# 03_MCU.net
KiCad netlist of a schematic drawn in Altium Designer
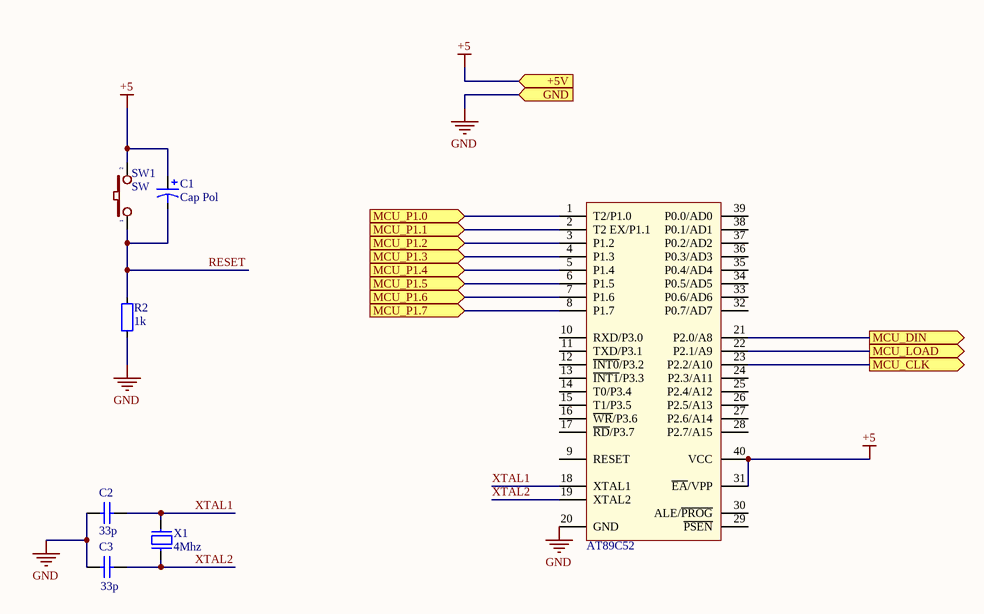
[diagram p0: [03] MCU.SchDoc]

(export (version "E")
  (design (tool "Eeschema 10.0.6"))
  (components
    (comp (ref "C1")
      (value "Cap Pol")
      (footprint "C3MM")
      (description "Polarized Capacitor (Axial)")
      (fields (field (name "PUBLISHER") "Altium Limited"))
      (libsource (lib "My Library") (part "Cap Pol"))
    )
    (comp (ref "C2")
      (value "33p")
      (footprint "CAP_CERAMIC")
      (description "Capacitor")
      (fields (field (name "Comment") "Capacitor Ceramic") (field (name "PUBLISHER") "Altium Limited"))
      (libsource (lib "My Library") (part "CapCeramic"))
    )
    (comp (ref "C3")
      (value "33p")
      (footprint "CAP_CERAMIC")
      (description "Capacitor")
      (fields (field (name "Comment") "Capacitor Ceramic") (field (name "PUBLISHER") "Altium Limited"))
      (libsource (lib "My Library") (part "CapCeramic"))
    )
    (comp (ref "IC1")
      (value "AT89C52")
      (footprint "DIP40/W0.6")
      (description "Atmel AT89C52, 8k Byte Flash Memory , 40 Pin")
      (libsource (lib "My Library") (part "AT89C52"))
    )
    (comp (ref "R2")
      (value "1k")
      (footprint "RES-1/2W")
      (description "Resistor - DIP")
      (libsource (lib "My Library") (part "Resistor - DIP"))
    )
    (comp (ref "SW1")
      (value "SW")
      (footprint "SW2")
      (description "Switch button 2 pin")
      (libsource (lib "My Library") (part "SW2"))
    )
    (comp (ref "X1")
      (value "4Mhz")
      (footprint "XT2")
      (description "Crystal For all Crystal 2pin.")
      (libsource (lib "My Library") (part "XT2"))
    )
  )
  (nets
    (net (code "1") (name "+5") (class "Default")
      (node (ref "C1") (pin "1") (pinfunction "1_1") (pintype "passive"))
      (node (ref "IC1") (pin "31") (pinfunction "~{EA}/VPP_31") (pintype "passive"))
      (node (ref "IC1") (pin "40") (pinfunction "VCC_40") (pintype "power_in"))
      (node (ref "SW1") (pin "2") (pinfunction "2_2") (pintype "passive"))
    )
    (net (code "2") (name "/MCU_CLK") (class "Default")
      (node (ref "IC1") (pin "23") (pinfunction "P2.2/A10_23") (pintype "passive"))
    )
    (net (code "3") (name "/MCU_DIN") (class "Default")
      (node (ref "IC1") (pin "21") (pinfunction "P2.0/A8_21") (pintype "passive"))
    )
    (net (code "4") (name "/MCU_LOAD") (class "Default")
      (node (ref "IC1") (pin "22") (pinfunction "P2.1/A9_22") (pintype "passive"))
    )
    (net (code "5") (name "/MCU_P1.0") (class "Default")
      (node (ref "IC1") (pin "1") (pinfunction "T2/P1.0_1") (pintype "passive"))
    )
    (net (code "6") (name "/MCU_P1.1") (class "Default")
      (node (ref "IC1") (pin "2") (pinfunction "T2_EX/P1.1_2") (pintype "passive"))
    )
    (net (code "7") (name "/MCU_P1.2") (class "Default")
      (node (ref "IC1") (pin "3") (pinfunction "P1.2_3") (pintype "passive"))
    )
    (net (code "8") (name "/MCU_P1.3") (class "Default")
      (node (ref "IC1") (pin "4") (pinfunction "P1.3_4") (pintype "passive"))
    )
    (net (code "9") (name "/MCU_P1.4") (class "Default")
      (node (ref "IC1") (pin "5") (pinfunction "P1.4_5") (pintype "passive"))
    )
    (net (code "10") (name "/MCU_P1.5") (class "Default")
      (node (ref "IC1") (pin "6") (pinfunction "P1.5_6") (pintype "passive"))
    )
    (net (code "11") (name "/MCU_P1.6") (class "Default")
      (node (ref "IC1") (pin "7") (pinfunction "P1.6_7") (pintype "passive"))
    )
    (net (code "12") (name "/MCU_P1.7") (class "Default")
      (node (ref "IC1") (pin "8") (pinfunction "P1.7_8") (pintype "passive"))
    )
    (net (code "13") (name "/RESET") (class "Default")
      (node (ref "C1") (pin "2") (pinfunction "2_2") (pintype "passive"))
      (node (ref "R2") (pin "2") (pinfunction "2_2") (pintype "passive"))
      (node (ref "SW1") (pin "1") (pinfunction "1_1") (pintype "passive"))
    )
    (net (code "14") (name "/XTAL1") (class "Default")
      (node (ref "C2") (pin "2") (pinfunction "2_2") (pintype "passive"))
      (node (ref "IC1") (pin "18") (pinfunction "XTAL1_18") (pintype "passive"))
      (node (ref "X1") (pin "2") (pinfunction "2_2") (pintype "passive"))
    )
    (net (code "15") (name "/XTAL2") (class "Default")
      (node (ref "C3") (pin "2") (pinfunction "2_2") (pintype "passive"))
      (node (ref "IC1") (pin "19") (pinfunction "XTAL2_19") (pintype "passive"))
      (node (ref "X1") (pin "1") (pinfunction "1_1") (pintype "passive"))
    )
    (net (code "16") (name "GND") (class "Default")
      (node (ref "C2") (pin "1") (pinfunction "1_1") (pintype "passive"))
      (node (ref "C3") (pin "1") (pinfunction "1_1") (pintype "passive"))
      (node (ref "IC1") (pin "20") (pinfunction "GND_20") (pintype "open_emitter"))
      (node (ref "R2") (pin "1") (pinfunction "1_1") (pintype "passive"))
    )
    (net (code "17") (name "unconnected-(IC1-ALE{slash}~{PROG}-Pad30)") (class "Default")
      (node (ref "IC1") (pin "30") (pinfunction "ALE/~{PROG}_30") (pintype "passive"))
    )
    (net (code "18") (name "unconnected-(IC1-P0.0{slash}AD0-Pad39)") (class "Default")
      (node (ref "IC1") (pin "39") (pinfunction "P0.0/AD0_39") (pintype "passive"))
    )
    (net (code "19") (name "unconnected-(IC1-P0.1{slash}AD1-Pad38)") (class "Default")
      (node (ref "IC1") (pin "38") (pinfunction "P0.1/AD1_38") (pintype "passive"))
    )
    (net (code "20") (name "unconnected-(IC1-P0.2{slash}AD2-Pad37)") (class "Default")
      (node (ref "IC1") (pin "37") (pinfunction "P0.2/AD2_37") (pintype "passive"))
    )
    (net (code "21") (name "unconnected-(IC1-P0.3{slash}AD3-Pad36)") (class "Default")
      (node (ref "IC1") (pin "36") (pinfunction "P0.3/AD3_36") (pintype "passive"))
    )
    (net (code "22") (name "unconnected-(IC1-P0.4{slash}AD4-Pad35)") (class "Default")
      (node (ref "IC1") (pin "35") (pinfunction "P0.4/AD4_35") (pintype "passive"))
    )
    (net (code "23") (name "unconnected-(IC1-P0.5{slash}AD5-Pad34)") (class "Default")
      (node (ref "IC1") (pin "34") (pinfunction "P0.5/AD5_34") (pintype "passive"))
    )
    (net (code "24") (name "unconnected-(IC1-P0.6{slash}AD6-Pad33)") (class "Default")
      (node (ref "IC1") (pin "33") (pinfunction "P0.6/AD6_33") (pintype "passive"))
    )
    (net (code "25") (name "unconnected-(IC1-P0.7{slash}AD7-Pad32)") (class "Default")
      (node (ref "IC1") (pin "32") (pinfunction "P0.7/AD7_32") (pintype "passive"))
    )
    (net (code "26") (name "unconnected-(IC1-P2.3{slash}A11-Pad24)") (class "Default")
      (node (ref "IC1") (pin "24") (pinfunction "P2.3/A11_24") (pintype "passive"))
    )
    (net (code "27") (name "unconnected-(IC1-P2.4{slash}A12-Pad25)") (class "Default")
      (node (ref "IC1") (pin "25") (pinfunction "P2.4/A12_25") (pintype "passive"))
    )
    (net (code "28") (name "unconnected-(IC1-P2.5{slash}A13-Pad26)") (class "Default")
      (node (ref "IC1") (pin "26") (pinfunction "P2.5/A13_26") (pintype "passive"))
    )
    (net (code "29") (name "unconnected-(IC1-P2.6{slash}A14-Pad27)") (class "Default")
      (node (ref "IC1") (pin "27") (pinfunction "P2.6/A14_27") (pintype "passive"))
    )
    (net (code "30") (name "unconnected-(IC1-P2.7{slash}A15-Pad28)") (class "Default")
      (node (ref "IC1") (pin "28") (pinfunction "P2.7/A15_28") (pintype "passive"))
    )
    (net (code "31") (name "unconnected-(IC1-RESET-Pad9)") (class "Default")
      (node (ref "IC1") (pin "9") (pinfunction "RESET_9") (pintype "passive"))
    )
    (net (code "32") (name "unconnected-(IC1-RXD{slash}P3.0-Pad10)") (class "Default")
      (node (ref "IC1") (pin "10") (pinfunction "RXD/P3.0_10") (pintype "passive"))
    )
    (net (code "33") (name "unconnected-(IC1-T0{slash}P3.4-Pad14)") (class "Default")
      (node (ref "IC1") (pin "14") (pinfunction "T0/P3.4_14") (pintype "passive"))
    )
    (net (code "34") (name "unconnected-(IC1-T1{slash}P3.5-Pad15)") (class "Default")
      (node (ref "IC1") (pin "15") (pinfunction "T1/P3.5_15") (pintype "passive"))
    )
    (net (code "35") (name "unconnected-(IC1-TXD{slash}P3.1-Pad11)") (class "Default")
      (node (ref "IC1") (pin "11") (pinfunction "TXD/P3.1_11") (pintype "passive"))
    )
    (net (code "36") (name "unconnected-(IC1-~{INT0}{slash}P3.2-Pad12)") (class "Default")
      (node (ref "IC1") (pin "12") (pinfunction "~{INT0}/P3.2_12") (pintype "passive"))
    )
    (net (code "37") (name "unconnected-(IC1-~{INT1}{slash}P3.3-Pad13)") (class "Default")
      (node (ref "IC1") (pin "13") (pinfunction "~{INT1}/P3.3_13") (pintype "passive"))
    )
    (net (code "38") (name "unconnected-(IC1-~{PSEN}-Pad29)") (class "Default")
      (node (ref "IC1") (pin "29") (pinfunction "~{PSEN}_29") (pintype "passive"))
    )
    (net (code "39") (name "unconnected-(IC1-~{RD}{slash}P3.7-Pad17)") (class "Default")
      (node (ref "IC1") (pin "17") (pinfunction "~{RD}/P3.7_17") (pintype "passive"))
    )
    (net (code "40") (name "unconnected-(IC1-~{WR}{slash}P3.6-Pad16)") (class "Default")
      (node (ref "IC1") (pin "16") (pinfunction "~{WR}/P3.6_16") (pintype "passive"))
    )
  )
)
